# psvemmc-v20.net
KiCad netlist of a schematic drawn in EAGLE
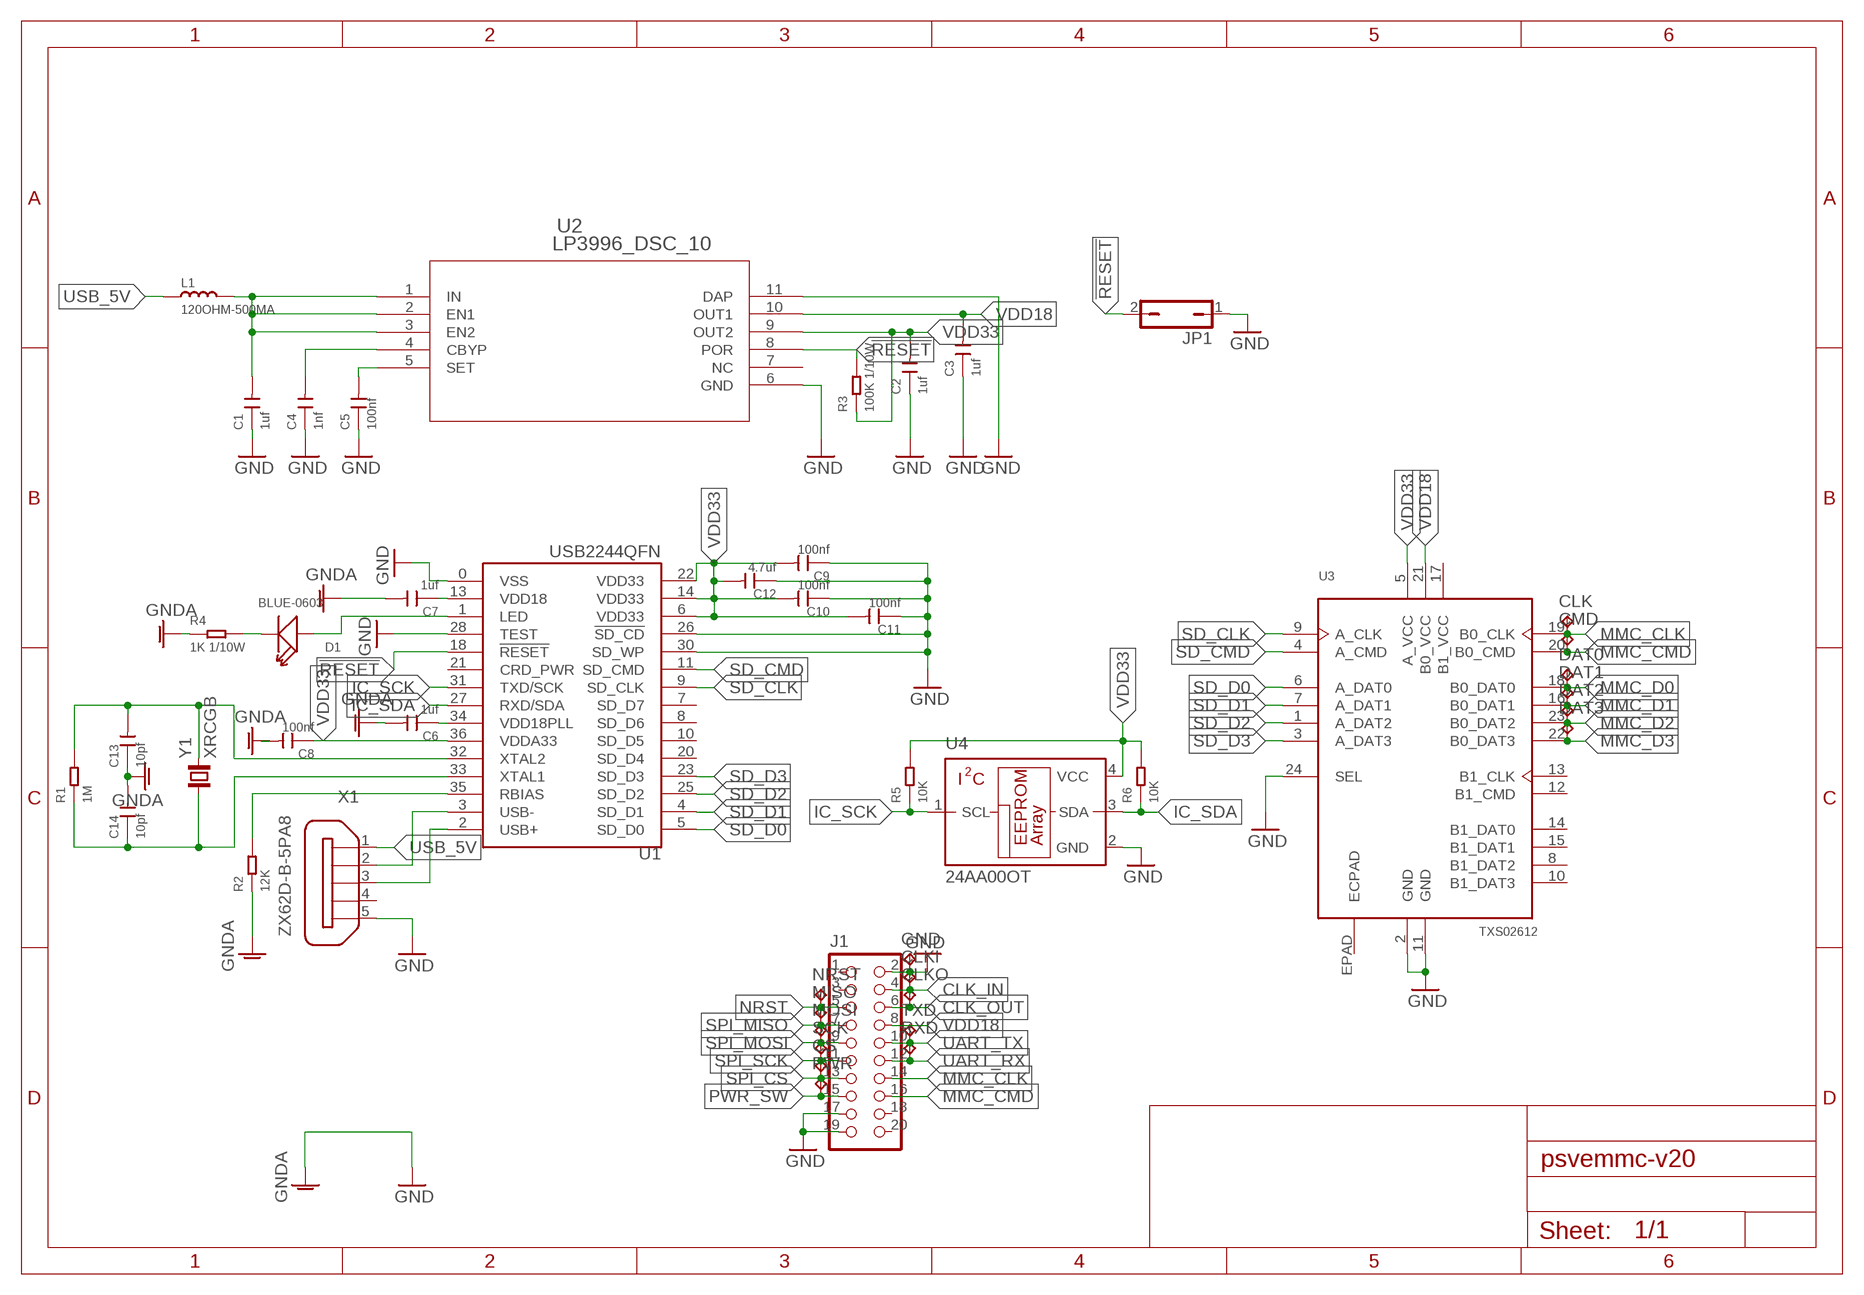
[diagram p0: schematic, sheet 1]

(export (version "E")
  (design (tool "Eeschema 10.0.6"))
  (components
    (comp (ref "C1")
      (value "1uf")
      (footprint "eagle-import:C0603")
      (fields (field (name "MPN") "CC0603KRX7R8BB105"))
      (libsource (lib "eagle-import") (part "CERAMIC-1UF-25V-10%-X7R(0603)"))
    )
    (comp (ref "C2")
      (value "1uf")
      (footprint "eagle-import:C0603")
      (fields (field (name "MPN") "CC0603KRX7R8BB105"))
      (libsource (lib "eagle-import") (part "CERAMIC-1UF-25V-10%-X7R(0603)"))
    )
    (comp (ref "C3")
      (value "1uf")
      (footprint "eagle-import:C0603")
      (fields (field (name "MPN") "CC0603KRX7R8BB105"))
      (libsource (lib "eagle-import") (part "CERAMIC-1UF-25V-10%-X7R(0603)"))
    )
    (comp (ref "C4")
      (value "1nf")
      (footprint "eagle-import:C0603")
      (fields (field (name "MPN") "GRM1885C1H102JA01D"))
      (libsource (lib "eagle-import") (part "CERAMIC-1NF-50V-5%-C0G(0603)"))
    )
    (comp (ref "C5")
      (value "100nf")
      (footprint "eagle-import:C0603")
      (fields (field (name "MPN") "CC0603KRX7R9BB104"))
      (libsource (lib "eagle-import") (part "CERAMIC-100NF-50V-10%-X7R(0603)"))
    )
    (comp (ref "C6")
      (value "1uf")
      (footprint "eagle-import:C0603")
      (fields (field (name "MPN") "CC0603KRX7R8BB105"))
      (libsource (lib "eagle-import") (part "CERAMIC-1UF-25V-10%-X7R(0603)"))
    )
    (comp (ref "C7")
      (value "1uf")
      (footprint "eagle-import:C0603")
      (fields (field (name "MPN") "CC0603KRX7R8BB105"))
      (libsource (lib "eagle-import") (part "CERAMIC-1UF-25V-10%-X7R(0603)"))
    )
    (comp (ref "C8")
      (value "100nf")
      (footprint "eagle-import:C0603")
      (fields (field (name "MPN") "CC0603KRX7R9BB104"))
      (libsource (lib "eagle-import") (part "CERAMIC-100NF-50V-10%-X7R(0603)"))
    )
    (comp (ref "C9")
      (value "100nf")
      (footprint "eagle-import:C0603")
      (fields (field (name "MPN") "CC0603KRX7R9BB104"))
      (libsource (lib "eagle-import") (part "CERAMIC-100NF-50V-10%-X7R(0603)"))
    )
    (comp (ref "C10")
      (value "100nf")
      (footprint "eagle-import:C0603")
      (fields (field (name "MPN") "CC0603KRX7R9BB104"))
      (libsource (lib "eagle-import") (part "CERAMIC-100NF-50V-10%-X7R(0603)"))
    )
    (comp (ref "C11")
      (value "100nf")
      (footprint "eagle-import:C0603")
      (fields (field (name "MPN") "CC0603KRX7R9BB104"))
      (libsource (lib "eagle-import") (part "CERAMIC-100NF-50V-10%-X7R(0603)"))
    )
    (comp (ref "C12")
      (value "4.7uf")
      (footprint "eagle-import:C0603")
      (fields (field (name "MPN") "CC0603KRX5R6BB475"))
      (libsource (lib "eagle-import") (part "CERAMIC-4.7UF-10V-10%-X5R(0603)"))
    )
    (comp (ref "C13")
      (value "10pf")
      (footprint "eagle-import:C0603")
      (fields (field (name "MPN") "CC0603JRNPO9BN100"))
      (libsource (lib "eagle-import") (part "CERAMIC-10PF-50V-5%-NPO(0603)"))
    )
    (comp (ref "C14")
      (value "10pf")
      (footprint "eagle-import:C0603")
      (fields (field (name "MPN") "CC0603JRNPO9BN100"))
      (libsource (lib "eagle-import") (part "CERAMIC-10PF-50V-5%-NPO(0603)"))
    )
    (comp (ref "CLK")
      (value "TPTP10R")
      (footprint "eagle-import:TP10R")
      (libsource (lib "eagle-import") (part "TPTP10R"))
    )
    (comp (ref "CLKI")
      (value "TPTP10R")
      (footprint "eagle-import:TP10R")
      (libsource (lib "eagle-import") (part "TPTP10R"))
    )
    (comp (ref "CLKO")
      (value "TPTP10R")
      (footprint "eagle-import:TP10R")
      (libsource (lib "eagle-import") (part "TPTP10R"))
    )
    (comp (ref "CMD")
      (value "TPTP10R")
      (footprint "eagle-import:TP10R")
      (libsource (lib "eagle-import") (part "TPTP10R"))
    )
    (comp (ref "CS")
      (value "TPTP10R")
      (footprint "eagle-import:TP10R")
      (libsource (lib "eagle-import") (part "TPTP10R"))
    )
    (comp (ref "D1")
      (value "BLUE-0603")
      (footprint "eagle-import:LED-0603")
      (fields (field (name "MPN") "19-217-BHC-ZL1M2RY-3T"))
      (libsource (lib "eagle-import") (part "SMD-LED-CLEAR-BLUE(0603)"))
    )
    (comp (ref "DAT0")
      (value "TPTP10R")
      (footprint "eagle-import:TP10R")
      (libsource (lib "eagle-import") (part "TPTP10R"))
    )
    (comp (ref "DAT1")
      (value "TPTP10R")
      (footprint "eagle-import:TP10R")
      (libsource (lib "eagle-import") (part "TPTP10R"))
    )
    (comp (ref "DAT2")
      (value "TPTP10R")
      (footprint "eagle-import:TP10R")
      (libsource (lib "eagle-import") (part "TPTP10R"))
    )
    (comp (ref "DAT3")
      (value "TPTP10R")
      (footprint "eagle-import:TP10R")
      (libsource (lib "eagle-import") (part "TPTP10R"))
    )
    (comp (ref "GND")
      (value "TPTP10R")
      (footprint "eagle-import:TP10R")
      (libsource (lib "eagle-import") (part "TPTP10R"))
    )
    (comp (ref "J1")
      (value "CON_HEADER_2X10-SHROUDED")
      (footprint "eagle-import:PINSHRD_PTH_2X10")
      (libsource (lib "eagle-import") (part "CON_HEADER_2X10-SHROUDED"))
    )
    (comp (ref "JP1")
      (value "JP1Q")
      (footprint "eagle-import:JP1")
      (libsource (lib "eagle-import") (part "JP1Q"))
    )
    (comp (ref "L1")
      (value "120OHM-500MA")
      (footprint "eagle-import:L0603")
      (fields (field (name "MPN") "BLM18AG121SN1D"))
      (libsource (lib "eagle-import") (part "SMD-FERRITE-CHIP-120-OHM-500MA(0603)"))
    )
    (comp (ref "MISO")
      (value "TPTP10R")
      (footprint "eagle-import:TP10R")
      (libsource (lib "eagle-import") (part "TPTP10R"))
    )
    (comp (ref "MOSI")
      (value "TPTP10R")
      (footprint "eagle-import:TP10R")
      (libsource (lib "eagle-import") (part "TPTP10R"))
    )
    (comp (ref "NRST")
      (value "TPTP10R")
      (footprint "eagle-import:TP10R")
      (libsource (lib "eagle-import") (part "TPTP10R"))
    )
    (comp (ref "PWR")
      (value "TPTP10R")
      (footprint "eagle-import:TP10R")
      (libsource (lib "eagle-import") (part "TPTP10R"))
    )
    (comp (ref "R1")
      (value "1M")
      (footprint "eagle-import:R0603")
      (fields (field (name "MPN") "RC0603FR-071ML"))
      (libsource (lib "eagle-import") (part "SMD-RES-1M-1%-1/10W(0603)"))
    )
    (comp (ref "R2")
      (value "12K")
      (footprint "eagle-import:R0603")
      (fields (field (name "MPN") "RC0603FR-0712KL"))
      (libsource (lib "eagle-import") (part "SMD-RES-12K-1%-1/10W(0603)"))
    )
    (comp (ref "R3")
      (value "100K 1/10W")
      (footprint "eagle-import:R0603")
      (fields (field (name "MPN") "RC0603JR-07100KL"))
      (libsource (lib "eagle-import") (part "SMD-RES-100K-5%-1/10W(0603)"))
    )
    (comp (ref "R4")
      (value "1K 1/10W")
      (footprint "eagle-import:R0603")
      (fields (field (name "MPN") "RC0603JR-071KL"))
      (libsource (lib "eagle-import") (part "SMD-RES-1K-5%-1/10W(0603)"))
    )
    (comp (ref "R5")
      (value "10K")
      (footprint "eagle-import:R0603")
      (fields (field (name "MPN") "RC0603FR-0710KL"))
      (libsource (lib "eagle-import") (part "SMD-RES-10K-1%-1/10W(0603)"))
    )
    (comp (ref "R6")
      (value "10K")
      (footprint "eagle-import:R0603")
      (fields (field (name "MPN") "RC0603FR-0710KL"))
      (libsource (lib "eagle-import") (part "SMD-RES-10K-1%-1/10W(0603)"))
    )
    (comp (ref "RXD")
      (value "TPTP10R")
      (footprint "eagle-import:TP10R")
      (libsource (lib "eagle-import") (part "TPTP10R"))
    )
    (comp (ref "SCK")
      (value "TPTP10R")
      (footprint "eagle-import:TP10R")
      (libsource (lib "eagle-import") (part "TPTP10R"))
    )
    (comp (ref "TXD")
      (value "TPTP10R")
      (footprint "eagle-import:TP10R")
      (libsource (lib "eagle-import") (part "TPTP10R"))
    )
    (comp (ref "U1")
      (value "USB2244QFN")
      (footprint "eagle-import:QFN36")
      (libsource (lib "eagle-import") (part "USB2244QFN"))
    )
    (comp (ref "U2")
      (value "LP3996_DSC_10")
      (footprint "eagle-import:SDA10A")
      (fields (field (name "PARTNUMBER") "LP3996SD0833"))
      (libsource (lib "eagle-import") (part "LP3996_DSC_10"))
    )
    (comp (ref "U3")
      (value "TXS02612")
      (footprint "eagle-import:S-PWQFN-N24")
      (libsource (lib "eagle-import") (part "TXS02612"))
    )
    (comp (ref "U4")
      (value "24AA00OT")
      (footprint "eagle-import:SOT23-5L")
      (fields (field (name "MF") "MICROCHIP") (field (name "MPN") "24AA00T-I/OTG"))
      (libsource (lib "eagle-import") (part "2400OTAA"))
    )
    (comp (ref "X1")
      (value "ZX62D-B-5PA8")
      (footprint "eagle-import:ZX62D-B-5PA8")
      (fields (field (name "MF") "Hirose"))
      (libsource (lib "eagle-import") (part "ZX62D-B-5PA8"))
    )
    (comp (ref "Y1")
      (value "XRCGB")
      (footprint "eagle-import:XRCGB")
      (libsource (lib "eagle-import") (part "XRCGB"))
    )
  )
  (nets
    (net (code "1") (name "/B1_VCC") (class "Default")
      (node (ref "U3") (pin "17") (pinfunction "B1_VCC_17") (pintype "power_in"))
    )
    (net (code "2") (name "/ECPAD") (class "Default")
      (node (ref "U3") (pin "EPAD") (pinfunction "ECPAD_EPAD") (pintype "power_in"))
    )
    (net (code "3") (name "/~{RESET}") (class "Default")
      (node (ref "JP1") (pin "2") (pinfunction "2_2") (pintype "passive"))
      (node (ref "R3") (pin "2") (pinfunction "2_2") (pintype "passive"))
      (node (ref "U1") (pin "18") (pinfunction "~{RESET}_18") (pintype "input"))
      (node (ref "U2") (pin "8") (pinfunction "POR_8") (pintype "passive"))
    )
    (net (code "4") (name "CLK_IN") (class "Default")
      (node (ref "CLKI") (pin "TP") (pinfunction "TP_TP") (pintype "input"))
      (node (ref "J1") (pin "4") (pinfunction "4_4") (pintype "passive"))
    )
    (net (code "5") (name "CLK_OUT") (class "Default")
      (node (ref "CLKO") (pin "TP") (pinfunction "TP_TP") (pintype "input"))
      (node (ref "J1") (pin "6") (pinfunction "6_6") (pintype "passive"))
    )
    (net (code "6") (name "GND") (class "Default")
      (node (ref "C1") (pin "1") (pinfunction "1_1") (pintype "passive"))
      (node (ref "C10") (pin "1") (pinfunction "1_1") (pintype "passive"))
      (node (ref "C11") (pin "1") (pinfunction "1_1") (pintype "passive"))
      (node (ref "C12") (pin "1") (pinfunction "1_1") (pintype "passive"))
      (node (ref "C13") (pin "1") (pinfunction "1_1") (pintype "passive"))
      (node (ref "C14") (pin "2") (pinfunction "2_2") (pintype "passive"))
      (node (ref "C2") (pin "1") (pinfunction "1_1") (pintype "passive"))
      (node (ref "C3") (pin "1") (pinfunction "1_1") (pintype "passive"))
      (node (ref "C4") (pin "1") (pinfunction "1_1") (pintype "passive"))
      (node (ref "C5") (pin "1") (pinfunction "1_1") (pintype "passive"))
      (node (ref "C6") (pin "2") (pinfunction "2_2") (pintype "passive"))
      (node (ref "C7") (pin "2") (pinfunction "2_2") (pintype "passive"))
      (node (ref "C8") (pin "2") (pinfunction "2_2") (pintype "passive"))
      (node (ref "C9") (pin "1") (pinfunction "1_1") (pintype "passive"))
      (node (ref "GND") (pin "TP") (pinfunction "TP_TP") (pintype "input"))
      (node (ref "J1") (pin "17") (pinfunction "17_17") (pintype "passive"))
      (node (ref "J1") (pin "19") (pinfunction "19_19") (pintype "passive"))
      (node (ref "J1") (pin "2") (pinfunction "2_2") (pintype "passive"))
      (node (ref "JP1") (pin "1") (pinfunction "1_1") (pintype "passive"))
      (node (ref "R2") (pin "1") (pinfunction "1_1") (pintype "passive"))
      (node (ref "R4") (pin "1") (pinfunction "1_1") (pintype "passive"))
      (node (ref "U1") (pin "0") (pinfunction "VSS_0") (pintype "bidirectional"))
      (node (ref "U1") (pin "26") (pinfunction "~{SD_CD}_26") (pintype "bidirectional"))
      (node (ref "U1") (pin "28") (pinfunction "TEST_28") (pintype "input"))
      (node (ref "U1") (pin "30") (pinfunction "SD_WP_30") (pintype "input"))
      (node (ref "U2") (pin "11") (pinfunction "DAP_11") (pintype "passive"))
      (node (ref "U2") (pin "6") (pinfunction "GND_6") (pintype "passive"))
      (node (ref "U3") (pin "11") (pinfunction "GND_11") (pintype "power_in"))
      (node (ref "U3") (pin "2") (pinfunction "GND_2") (pintype "power_in"))
      (node (ref "U3") (pin "24") (pinfunction "SEL_24") (pintype "input"))
      (node (ref "U4") (pin "2") (pinfunction "GND_2") (pintype "power_in"))
      (node (ref "X1") (pin "5") (pinfunction "5_5") (pintype "passive"))
    )
    (net (code "7") (name "IC_SCK") (class "Default")
      (node (ref "R5") (pin "1") (pinfunction "1_1") (pintype "passive"))
      (node (ref "U1") (pin "31") (pinfunction "TXD/SCK_31") (pintype "bidirectional"))
      (node (ref "U4") (pin "1") (pinfunction "SCL_1") (pintype "input"))
    )
    (net (code "8") (name "IC_SDA") (class "Default")
      (node (ref "R6") (pin "1") (pinfunction "1_1") (pintype "passive"))
      (node (ref "U1") (pin "27") (pinfunction "RXD/SDA_27") (pintype "bidirectional"))
      (node (ref "U4") (pin "3") (pinfunction "SDA_3") (pintype "bidirectional"))
    )
    (net (code "9") (name "MMC_CLK") (class "Default")
      (node (ref "CLK") (pin "TP") (pinfunction "TP_TP") (pintype "input"))
      (node (ref "J1") (pin "14") (pinfunction "14_14") (pintype "passive"))
      (node (ref "U3") (pin "19") (pinfunction "B0_CLK_19") (pintype "output"))
    )
    (net (code "10") (name "MMC_CMD") (class "Default")
      (node (ref "CMD") (pin "TP") (pinfunction "TP_TP") (pintype "input"))
      (node (ref "J1") (pin "16") (pinfunction "16_16") (pintype "passive"))
      (node (ref "U3") (pin "20") (pinfunction "B0_CMD_20") (pintype "bidirectional"))
    )
    (net (code "11") (name "MMC_D0") (class "Default")
      (node (ref "DAT0") (pin "TP") (pinfunction "TP_TP") (pintype "input"))
      (node (ref "U3") (pin "18") (pinfunction "B0_DAT0_18") (pintype "bidirectional"))
    )
    (net (code "12") (name "MMC_D1") (class "Default")
      (node (ref "DAT1") (pin "TP") (pinfunction "TP_TP") (pintype "input"))
      (node (ref "U3") (pin "16") (pinfunction "B0_DAT1_16") (pintype "bidirectional"))
    )
    (net (code "13") (name "MMC_D2") (class "Default")
      (node (ref "DAT2") (pin "TP") (pinfunction "TP_TP") (pintype "input"))
      (node (ref "U3") (pin "23") (pinfunction "B0_DAT2_23") (pintype "bidirectional"))
    )
    (net (code "14") (name "MMC_D3") (class "Default")
      (node (ref "DAT3") (pin "TP") (pinfunction "TP_TP") (pintype "input"))
      (node (ref "U3") (pin "22") (pinfunction "B0_DAT3_22") (pintype "bidirectional"))
    )
    (net (code "15") (name "NRST") (class "Default")
      (node (ref "J1") (pin "5") (pinfunction "5_5") (pintype "passive"))
      (node (ref "NRST") (pin "TP") (pinfunction "TP_TP") (pintype "input"))
    )
    (net (code "16") (name "Net-(D1-Pad-)") (class "Default")
      (node (ref "D1") (pin "-") (pinfunction "-_-") (pintype "passive"))
      (node (ref "R4") (pin "2") (pinfunction "2_2") (pintype "passive"))
    )
    (net (code "17") (name "Net-(U1-LED)") (class "Default")
      (node (ref "D1") (pin "+") (pinfunction "+_+") (pintype "passive"))
      (node (ref "U1") (pin "1") (pinfunction "LED_1") (pintype "bidirectional"))
    )
    (net (code "18") (name "Net-(U1-RBIAS)") (class "Default")
      (node (ref "R2") (pin "2") (pinfunction "2_2") (pintype "passive"))
      (node (ref "U1") (pin "35") (pinfunction "RBIAS_35") (pintype "bidirectional"))
    )
    (net (code "19") (name "Net-(U1-USB+)") (class "Default")
      (node (ref "U1") (pin "2") (pinfunction "USB+_2") (pintype "bidirectional"))
      (node (ref "X1") (pin "3") (pinfunction "3_3") (pintype "passive"))
    )
    (net (code "20") (name "Net-(U1-USB-)") (class "Default")
      (node (ref "U1") (pin "3") (pinfunction "USB-_3") (pintype "bidirectional"))
      (node (ref "X1") (pin "2") (pinfunction "2_2") (pintype "passive"))
    )
    (net (code "21") (name "Net-(U1-VDD18)") (class "Default")
      (node (ref "C7") (pin "1") (pinfunction "1_1") (pintype "passive"))
      (node (ref "U1") (pin "13") (pinfunction "VDD18_13") (pintype "bidirectional"))
    )
    (net (code "22") (name "Net-(U1-VDD18PLL)") (class "Default")
      (node (ref "C6") (pin "1") (pinfunction "1_1") (pintype "passive"))
      (node (ref "U1") (pin "34") (pinfunction "VDD18PLL_34") (pintype "bidirectional"))
    )
    (net (code "23") (name "Net-(U1-XTAL1)") (class "Default")
      (node (ref "C14") (pin "1") (pinfunction "1_1") (pintype "passive"))
      (node (ref "R1") (pin "1") (pinfunction "1_1") (pintype "passive"))
      (node (ref "U1") (pin "33") (pinfunction "XTAL1_33") (pintype "input"))
      (node (ref "Y1") (pin "1") (pinfunction "1_1") (pintype "passive"))
    )
    (net (code "24") (name "Net-(U1-XTAL2)") (class "Default")
      (node (ref "C13") (pin "2") (pinfunction "2_2") (pintype "passive"))
      (node (ref "R1") (pin "2") (pinfunction "2_2") (pintype "passive"))
      (node (ref "U1") (pin "32") (pinfunction "XTAL2_32") (pintype "output"))
      (node (ref "Y1") (pin "3") (pinfunction "2_3") (pintype "passive"))
    )
    (net (code "25") (name "Net-(U2-CBYP)") (class "Default")
      (node (ref "C4") (pin "2") (pinfunction "2_2") (pintype "passive"))
      (node (ref "U2") (pin "4") (pinfunction "CBYP_4") (pintype "passive"))
    )
    (net (code "26") (name "Net-(U2-EN1)") (class "Default")
      (node (ref "C1") (pin "2") (pinfunction "2_2") (pintype "passive"))
      (node (ref "L1") (pin "2") (pinfunction "2_2") (pintype "passive"))
      (node (ref "U2") (pin "1") (pinfunction "IN_1") (pintype "input"))
      (node (ref "U2") (pin "2") (pinfunction "EN1_2") (pintype "passive"))
      (node (ref "U2") (pin "3") (pinfunction "EN2_3") (pintype "passive"))
    )
    (net (code "27") (name "Net-(U2-SET)") (class "Default")
      (node (ref "C5") (pin "2") (pinfunction "2_2") (pintype "passive"))
      (node (ref "U2") (pin "5") (pinfunction "SET_5") (pintype "passive"))
    )
    (net (code "28") (name "PWR_SW") (class "Default")
      (node (ref "J1") (pin "15") (pinfunction "15_15") (pintype "passive"))
      (node (ref "PWR") (pin "TP") (pinfunction "TP_TP") (pintype "input"))
    )
    (net (code "29") (name "SD_CLK") (class "Default")
      (node (ref "U1") (pin "9") (pinfunction "SD_CLK_9") (pintype "output"))
      (node (ref "U3") (pin "9") (pinfunction "A_CLK_9") (pintype "input"))
    )
    (net (code "30") (name "SD_CMD") (class "Default")
      (node (ref "U1") (pin "11") (pinfunction "SD_CMD_11") (pintype "bidirectional"))
      (node (ref "U3") (pin "4") (pinfunction "A_CMD_4") (pintype "bidirectional"))
    )
    (net (code "31") (name "SD_D0") (class "Default")
      (node (ref "U1") (pin "5") (pinfunction "SD_D0_5") (pintype "bidirectional"))
      (node (ref "U3") (pin "6") (pinfunction "A_DAT0_6") (pintype "bidirectional"))
    )
    (net (code "32") (name "SD_D1") (class "Default")
      (node (ref "U1") (pin "4") (pinfunction "SD_D1_4") (pintype "bidirectional"))
      (node (ref "U3") (pin "7") (pinfunction "A_DAT1_7") (pintype "bidirectional"))
    )
    (net (code "33") (name "SD_D2") (class "Default")
      (node (ref "U1") (pin "25") (pinfunction "SD_D2_25") (pintype "bidirectional"))
      (node (ref "U3") (pin "1") (pinfunction "A_DAT2_1") (pintype "bidirectional"))
    )
    (net (code "34") (name "SD_D3") (class "Default")
      (node (ref "U1") (pin "23") (pinfunction "SD_D3_23") (pintype "bidirectional"))
      (node (ref "U3") (pin "3") (pinfunction "A_DAT3_3") (pintype "bidirectional"))
    )
    (net (code "35") (name "SPI_CS") (class "Default")
      (node (ref "CS") (pin "TP") (pinfunction "TP_TP") (pintype "input"))
      (node (ref "J1") (pin "13") (pinfunction "13_13") (pintype "passive"))
    )
    (net (code "36") (name "SPI_MISO") (class "Default")
      (node (ref "J1") (pin "7") (pinfunction "7_7") (pintype "passive"))
      (node (ref "MISO") (pin "TP") (pinfunction "TP_TP") (pintype "input"))
    )
    (net (code "37") (name "SPI_MOSI") (class "Default")
      (node (ref "J1") (pin "9") (pinfunction "9_9") (pintype "passive"))
      (node (ref "MOSI") (pin "TP") (pinfunction "TP_TP") (pintype "input"))
    )
    (net (code "38") (name "SPI_SCK") (class "Default")
      (node (ref "J1") (pin "11") (pinfunction "11_11") (pintype "passive"))
      (node (ref "SCK") (pin "TP") (pinfunction "TP_TP") (pintype "input"))
    )
    (net (code "39") (name "UART_RX") (class "Default")
      (node (ref "J1") (pin "12") (pinfunction "12_12") (pintype "passive"))
      (node (ref "RXD") (pin "TP") (pinfunction "TP_TP") (pintype "input"))
    )
    (net (code "40") (name "UART_TX") (class "Default")
      (node (ref "J1") (pin "10") (pinfunction "10_10") (pintype "passive"))
      (node (ref "TXD") (pin "TP") (pinfunction "TP_TP") (pintype "input"))
    )
    (net (code "41") (name "USB_5V") (class "Default")
      (node (ref "L1") (pin "1") (pinfunction "1_1") (pintype "passive"))
      (node (ref "X1") (pin "1") (pinfunction "1_1") (pintype "passive"))
    )
    (net (code "42") (name "VDD18") (class "Default")
      (node (ref "C3") (pin "2") (pinfunction "2_2") (pintype "passive"))
      (node (ref "J1") (pin "8") (pinfunction "8_8") (pintype "passive"))
      (node (ref "U2") (pin "10") (pinfunction "OUT1_10") (pintype "output"))
      (node (ref "U3") (pin "21") (pinfunction "B0_VCC_21") (pintype "power_in"))
    )
    (net (code "43") (name "VDD33") (class "Default")
      (node (ref "C10") (pin "2") (pinfunction "2_2") (pintype "passive"))
      (node (ref "C11") (pin "2") (pinfunction "2_2") (pintype "passive"))
      (node (ref "C12") (pin "2") (pinfunction "2_2") (pintype "passive"))
      (node (ref "C2") (pin "2") (pinfunction "2_2") (pintype "passive"))
      (node (ref "C8") (pin "1") (pinfunction "1_1") (pintype "passive"))
      (node (ref "C9") (pin "2") (pinfunction "2_2") (pintype "passive"))
      (node (ref "R3") (pin "1") (pinfunction "1_1") (pintype "passive"))
      (node (ref "R5") (pin "2") (pinfunction "2_2") (pintype "passive"))
      (node (ref "R6") (pin "2") (pinfunction "2_2") (pintype "passive"))
      (node (ref "U1") (pin "14") (pinfunction "VDD33_14") (pintype "bidirectional"))
      (node (ref "U1") (pin "22") (pinfunction "VDD33_22") (pintype "bidirectional"))
      (node (ref "U1") (pin "36") (pinfunction "VDDA33_36") (pintype "bidirectional"))
      (node (ref "U1") (pin "6") (pinfunction "VDD33_6") (pintype "bidirectional"))
      (node (ref "U2") (pin "9") (pinfunction "OUT2_9") (pintype "output"))
      (node (ref "U3") (pin "5") (pinfunction "A_VCC_5") (pintype "power_in"))
      (node (ref "U4") (pin "4") (pinfunction "VCC_4") (pintype "power_in"))
    )
    (net (code "44") (name "unconnected-(J1-Pad1)") (class "Default")
      (node (ref "J1") (pin "1") (pinfunction "1_1") (pintype "passive"))
    )
    (net (code "45") (name "unconnected-(J1-Pad3)") (class "Default")
      (node (ref "J1") (pin "3") (pinfunction "3_3") (pintype "passive"))
    )
    (net (code "46") (name "unconnected-(J1-Pad18)") (class "Default")
      (node (ref "J1") (pin "18") (pinfunction "18_18") (pintype "passive"))
    )
    (net (code "47") (name "unconnected-(J1-Pad20)") (class "Default")
      (node (ref "J1") (pin "20") (pinfunction "20_20") (pintype "passive"))
    )
    (net (code "48") (name "unconnected-(U1-CRD_PWR-Pad21)") (class "Default")
      (node (ref "U1") (pin "21") (pinfunction "CRD_PWR_21") (pintype "bidirectional"))
    )
    (net (code "49") (name "unconnected-(U1-SD_D4-Pad20)") (class "Default")
      (node (ref "U1") (pin "20") (pinfunction "SD_D4_20") (pintype "bidirectional"))
    )
    (net (code "50") (name "unconnected-(U1-SD_D5-Pad10)") (class "Default")
      (node (ref "U1") (pin "10") (pinfunction "SD_D5_10") (pintype "bidirectional"))
    )
    (net (code "51") (name "unconnected-(U1-SD_D6-Pad8)") (class "Default")
      (node (ref "U1") (pin "8") (pinfunction "SD_D6_8") (pintype "bidirectional"))
    )
    (net (code "52") (name "unconnected-(U1-SD_D7-Pad7)") (class "Default")
      (node (ref "U1") (pin "7") (pinfunction "SD_D7_7") (pintype "bidirectional"))
    )
    (net (code "53") (name "unconnected-(U2-NC-Pad7)") (class "Default")
      (node (ref "U2") (pin "7") (pinfunction "NC_7") (pintype "passive"))
    )
    (net (code "54") (name "unconnected-(U3-B1_CLK-Pad13)") (class "Default")
      (node (ref "U3") (pin "13") (pinfunction "B1_CLK_13") (pintype "output"))
    )
    (net (code "55") (name "unconnected-(U3-B1_CMD-Pad12)") (class "Default")
      (node (ref "U3") (pin "12") (pinfunction "B1_CMD_12") (pintype "bidirectional"))
    )
    (net (code "56") (name "unconnected-(U3-B1_DAT0-Pad14)") (class "Default")
      (node (ref "U3") (pin "14") (pinfunction "B1_DAT0_14") (pintype "bidirectional"))
    )
    (net (code "57") (name "unconnected-(U3-B1_DAT1-Pad15)") (class "Default")
      (node (ref "U3") (pin "15") (pinfunction "B1_DAT1_15") (pintype "bidirectional"))
    )
    (net (code "58") (name "unconnected-(U3-B1_DAT2-Pad8)") (class "Default")
      (node (ref "U3") (pin "8") (pinfunction "B1_DAT2_8") (pintype "bidirectional"))
    )
    (net (code "59") (name "unconnected-(U3-B1_DAT3-Pad10)") (class "Default")
      (node (ref "U3") (pin "10") (pinfunction "B1_DAT3_10") (pintype "bidirectional"))
    )
    (net (code "60") (name "unconnected-(X1-Pad4)") (class "Default")
      (node (ref "X1") (pin "4") (pinfunction "4_4") (pintype "passive"))
    )
  )
)
